# STM32F103RE.net
KiCad netlist of a schematic drawn in Altium Designer
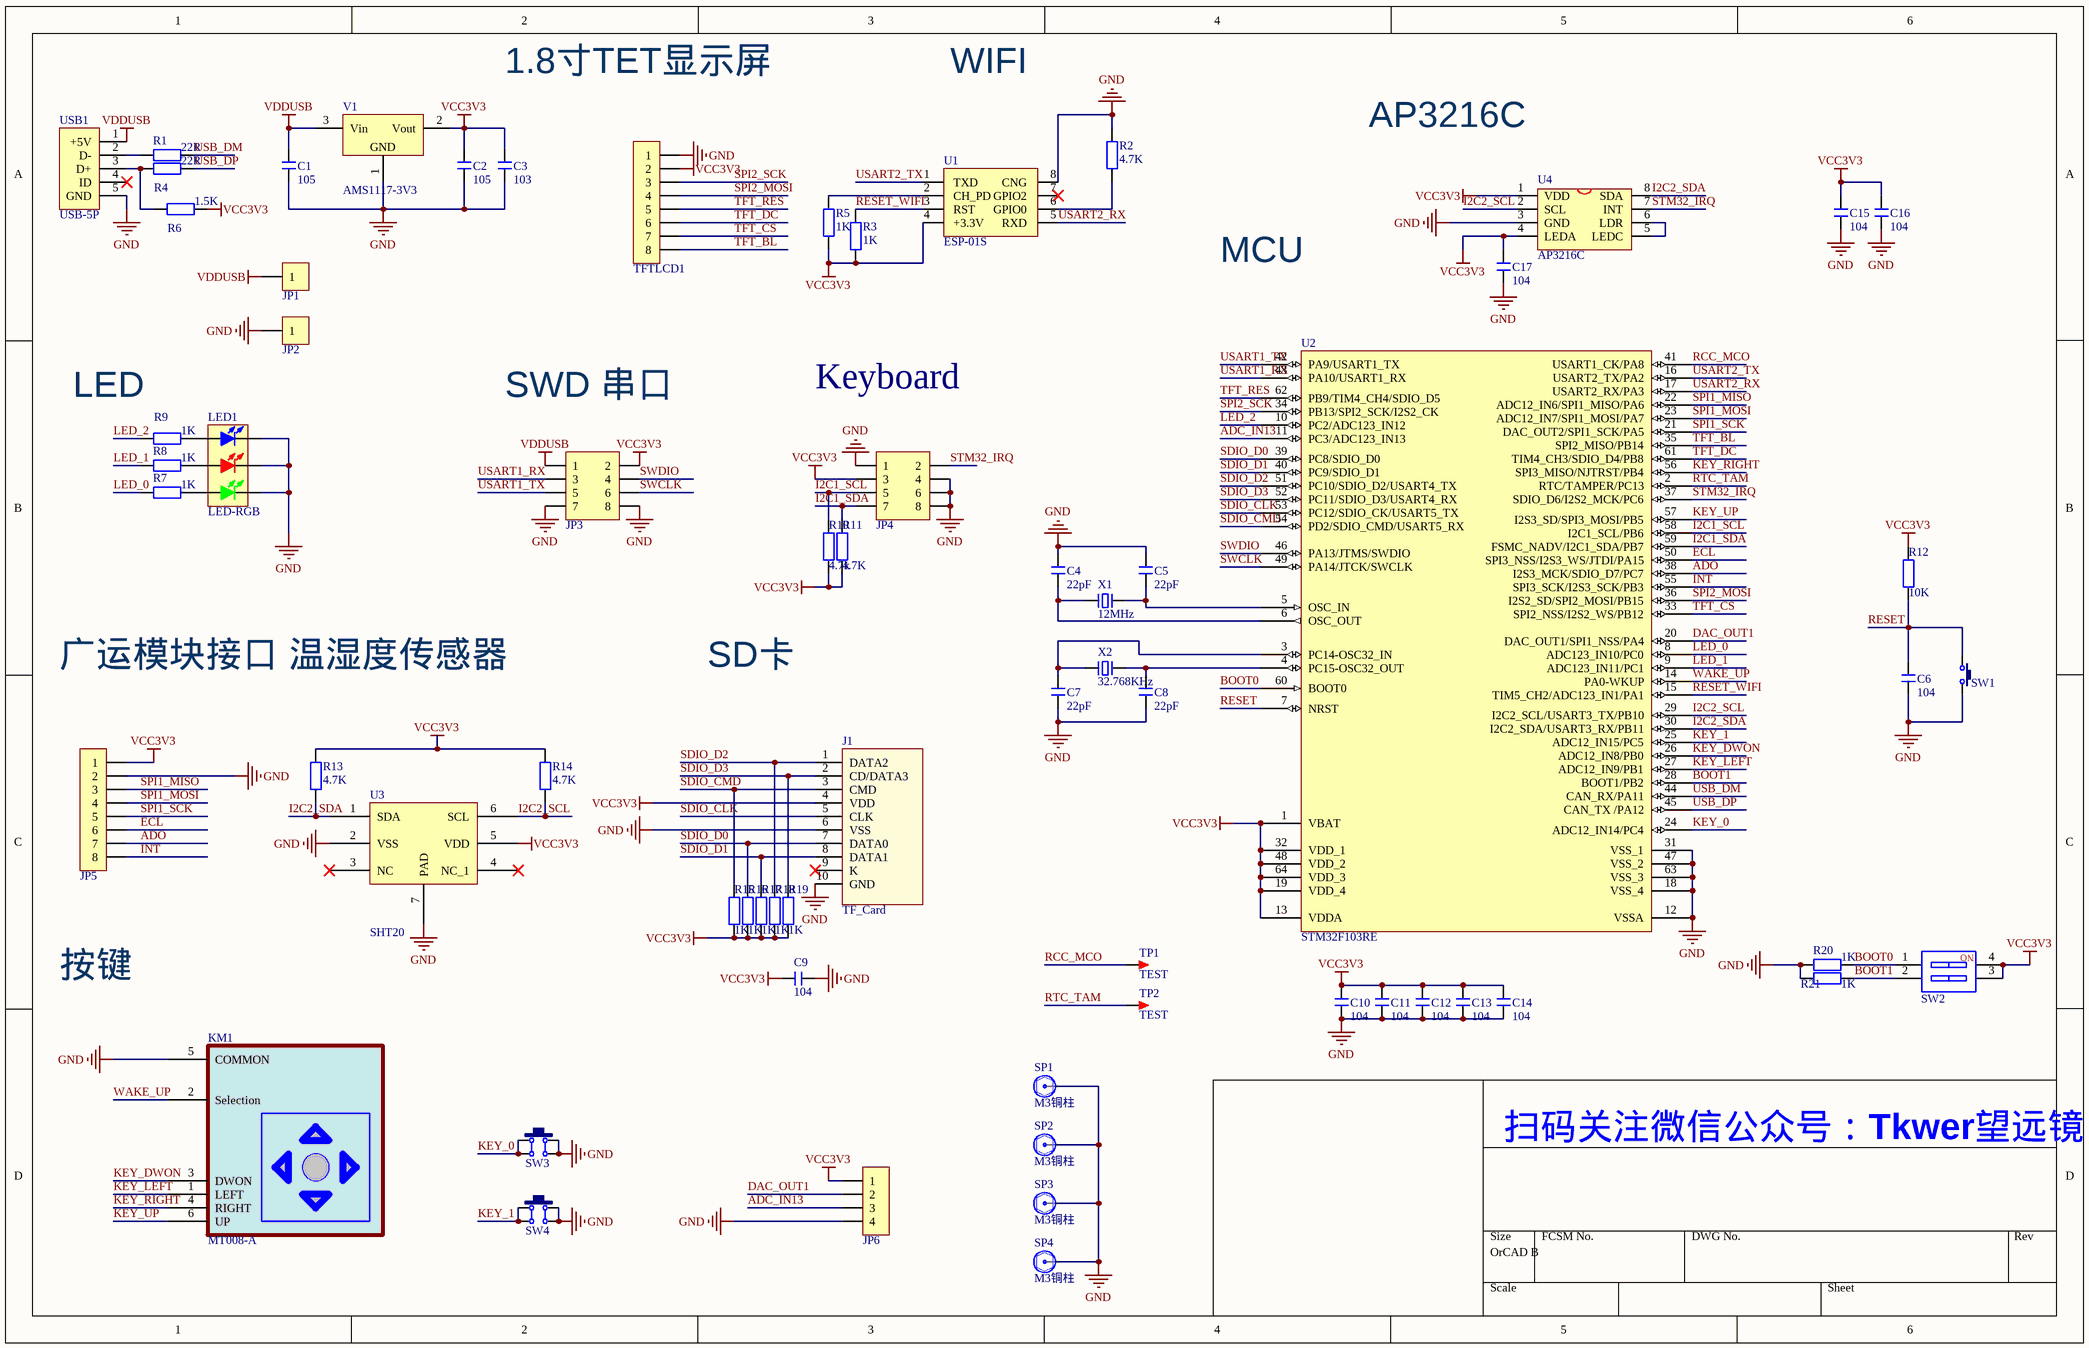
[diagram p0: STM32F103RE.SchDoc]

(export (version "E")
  (design (tool "Eeschema 10.0.6"))
  (components
    (comp (ref "C1")
      (value "105")
      (footprint "C 0805_L")
      (description "无极性贴片电容")
      (fields (field (name "版权归属") "源创客"))
      (libsource (lib "3.1   - 电阻-电容-电感") (part "C"))
    )
    (comp (ref "C2")
      (value "105")
      (footprint "C 0805_L")
      (description "无极性贴片电容")
      (fields (field (name "版权归属") "源创客"))
      (libsource (lib "3.1   - 电阻-电容-电感") (part "C"))
    )
    (comp (ref "C3")
      (value "103")
      (footprint "C 0603_L")
      (description "无极性贴片电容")
      (fields (field (name "版权归属") "源创客"))
      (libsource (lib "3.1   - 电阻-电容-电感") (part "C"))
    )
    (comp (ref "C4")
      (value "22pF")
      (footprint "C 0603_L")
      (description "无极性贴片电容")
      (fields (field (name "版权归属") "源创客"))
      (libsource (lib "3.1   - 电阻-电容-电感") (part "C"))
    )
    (comp (ref "C5")
      (value "22pF")
      (footprint "C 0603_L")
      (description "无极性贴片电容")
      (fields (field (name "版权归属") "源创客"))
      (libsource (lib "3.1   - 电阻-电容-电感") (part "C"))
    )
    (comp (ref "C6")
      (value "104")
      (footprint "C 0603_L")
      (description "无极性贴片电容")
      (fields (field (name "版权归属") "源创客"))
      (libsource (lib "3.1   - 电阻-电容-电感") (part "C"))
    )
    (comp (ref "C7")
      (value "22pF")
      (footprint "C 0603_L")
      (description "无极性贴片电容")
      (fields (field (name "版权归属") "源创客"))
      (libsource (lib "3.1   - 电阻-电容-电感") (part "C"))
    )
    (comp (ref "C8")
      (value "22pF")
      (footprint "C 0603_L")
      (description "无极性贴片电容")
      (fields (field (name "版权归属") "源创客"))
      (libsource (lib "3.1   - 电阻-电容-电感") (part "C"))
    )
    (comp (ref "C9")
      (value "104")
      (footprint "C 0603_L")
      (description "无极性贴片电容")
      (fields (field (name "版权归属") "源创客"))
      (libsource (lib "电阻-电容-电感") (part "C"))
    )
    (comp (ref "C10")
      (value "104")
      (footprint "C 0603_L")
      (description "无极性贴片电容")
      (fields (field (name "版权归属") "源创客"))
      (libsource (lib "3.1   - 电阻-电容-电感") (part "C"))
    )
    (comp (ref "C11")
      (value "104")
      (footprint "C 0603_L")
      (description "无极性贴片电容")
      (fields (field (name "版权归属") "源创客"))
      (libsource (lib "3.1   - 电阻-电容-电感") (part "C"))
    )
    (comp (ref "C12")
      (value "104")
      (footprint "C 0603_L")
      (description "无极性贴片电容")
      (fields (field (name "版权归属") "源创客"))
      (libsource (lib "3.1   - 电阻-电容-电感") (part "C"))
    )
    (comp (ref "C13")
      (value "104")
      (footprint "C 0603_L")
      (description "无极性贴片电容")
      (fields (field (name "版权归属") "源创客"))
      (libsource (lib "3.1   - 电阻-电容-电感") (part "C"))
    )
    (comp (ref "C14")
      (value "104")
      (footprint "C 0603_L")
      (description "无极性贴片电容")
      (fields (field (name "版权归属") "源创客"))
      (libsource (lib "3.1   - 电阻-电容-电感") (part "C"))
    )
    (comp (ref "C15")
      (value "104")
      (footprint "C 0603_L")
      (description "无极性贴片电容")
      (fields (field (name "版权归属") "源创客"))
      (libsource (lib "3.1   - 电阻-电容-电感") (part "C"))
    )
    (comp (ref "C16")
      (value "104")
      (footprint "C 0603_L")
      (description "无极性贴片电容")
      (fields (field (name "版权归属") "源创客"))
      (libsource (lib "3.1   - 电阻-电容-电感") (part "C"))
    )
    (comp (ref "C17")
      (value "104")
      (footprint "C 0603_L")
      (description "无极性贴片电容")
      (fields (field (name "版权归属") "源创客"))
      (libsource (lib "3.1   - 电阻-电容-电感") (part "C"))
    )
    (comp (ref "J1")
      (value "TF_Card")
      (footprint "Micro SD")
      (description "TF卡座")
      (fields (field (name "版权归属") "源创客"))
      (libsource (lib "4.1   - 接口类") (part "TF_Card"))
    )
    (comp (ref "JP1")
      (value "HDR-1X1")
      (footprint "HDR2.54-LI-1P")
      (description "1P接插件")
      (fields (field (name "版权归属") "源创客"))
      (libsource (lib "接插件") (part "Header 1"))
    )
    (comp (ref "JP2")
      (value "HDR-1X1")
      (footprint "HDR2.54-LI-1P")
      (description "1P接插件")
      (fields (field (name "版权归属") "源创客"))
      (libsource (lib "接插件") (part "Header 1"))
    )
    (comp (ref "JP3")
      (value "Header 4X2")
      (footprint "HDR2.54-WI-2x4P")
      (description "4*2P接插件")
      (fields (field (name "版权归属") "源创客"))
      (libsource (lib "4.5   - 接插件-脚距2.54") (part "Header 4X2"))
    )
    (comp (ref "JP4")
      (value "Header 4X2")
      (footprint "HDR2.54-WI-2x4P")
      (description "4*2P接插件")
      (fields (field (name "版权归属") "源创客"))
      (libsource (lib "4.5   - 接插件-脚距2.54") (part "Header 4X2"))
    )
    (comp (ref "JP5")
      (value "HDR-1X8")
      (footprint "HDR2.54-M-LI-8P")
      (description "8P接插件")
      (fields (field (name "版权归属") "源创客"))
      (libsource (lib "4.5   - 接插件-脚距2.54") (part "Header 8"))
    )
    (comp (ref "JP6")
      (value "HDR-1X4")
      (footprint "HDR2.54-LI-4P")
      (description "4P接插件")
      (fields (field (name "版权归属") "源创客"))
      (libsource (lib "4.5   - 接插件-脚距2.54") (part "Header 4"))
    )
    (comp (ref "KM1")
      (value "MT008-A")
      (footprint "JOY_MT008-A")
      (libsource (lib "13.1 - 模块") (part "MT-008A"))
    )
    (comp (ref "LED1")
      (value "LED-RGB")
      (footprint "LED 5050")
      (description "三基色LED")
      (fields (field (name "版权归属") "源创客"))
      (libsource (lib "9.1   - LED") (part "LED-RGB"))
    )
    (comp (ref "R1")
      (value "22R")
      (footprint "R 0603_L")
      (description "贴片电阻")
      (fields (field (name "版权归属") "源创客"))
      (libsource (lib "3.1   - 电阻-电容-电感") (part "R"))
    )
    (comp (ref "R2")
      (value "4.7K")
      (footprint "R 0603_L")
      (description "贴片电阻")
      (fields (field (name "版权归属") "源创客"))
      (libsource (lib "3.1   - 电阻-电容-电感") (part "R"))
    )
    (comp (ref "R3")
      (value "1K")
      (footprint "R 0603_L")
      (description "贴片电阻")
      (fields (field (name "版权归属") "源创客"))
      (libsource (lib "3.1   - 电阻-电容-电感") (part "R"))
    )
    (comp (ref "R4")
      (value "22R")
      (footprint "R 0603_L")
      (description "贴片电阻")
      (fields (field (name "版权归属") "源创客"))
      (libsource (lib "3.1   - 电阻-电容-电感") (part "R"))
    )
    (comp (ref "R5")
      (value "1K")
      (footprint "R 0603_L")
      (description "贴片电阻")
      (fields (field (name "版权归属") "源创客"))
      (libsource (lib "3.1   - 电阻-电容-电感") (part "R"))
    )
    (comp (ref "R6")
      (value "1.5K")
      (footprint "R 0603_L")
      (description "贴片电阻")
      (fields (field (name "版权归属") "源创客"))
      (libsource (lib "3.1   - 电阻-电容-电感") (part "R"))
    )
    (comp (ref "R7")
      (value "1K")
      (footprint "R 0603_L")
      (description "贴片电阻")
      (fields (field (name "版权归属") "源创客"))
      (libsource (lib "3.1   - 电阻-电容-电感") (part "R"))
    )
    (comp (ref "R8")
      (value "1K")
      (footprint "R 0603_L")
      (description "贴片电阻")
      (fields (field (name "版权归属") "源创客"))
      (libsource (lib "3.1   - 电阻-电容-电感") (part "R"))
    )
    (comp (ref "R9")
      (value "1K")
      (footprint "R 0603_L")
      (description "贴片电阻")
      (fields (field (name "版权归属") "源创客"))
      (libsource (lib "3.1   - 电阻-电容-电感") (part "R"))
    )
    (comp (ref "R10")
      (value "4.7k")
      (footprint "R 0603_L")
      (description "贴片电阻")
      (fields (field (name "版权归属") "源创客"))
      (libsource (lib "电阻-电容-电感") (part "R"))
    )
    (comp (ref "R11")
      (value "4.7K")
      (footprint "R 0603_L")
      (description "贴片电阻")
      (fields (field (name "版权归属") "源创客"))
      (libsource (lib "电阻-电容-电感") (part "R"))
    )
    (comp (ref "R12")
      (value "10K")
      (footprint "R 0603_L")
      (description "贴片电阻")
      (fields (field (name "版权归属") "源创客"))
      (libsource (lib "电阻-电容-电感") (part "R"))
    )
    (comp (ref "R13")
      (value "4.7K")
      (footprint "R 0603_L")
      (description "贴片电阻")
      (fields (field (name "版权归属") "源创客"))
      (libsource (lib "3.1   - 电阻-电容-电感") (part "R"))
    )
    (comp (ref "R14")
      (value "4.7K")
      (footprint "R 0603_L")
      (description "贴片电阻")
      (fields (field (name "版权归属") "源创客"))
      (libsource (lib "3.1   - 电阻-电容-电感") (part "R"))
    )
    (comp (ref "R15")
      (value "1K")
      (footprint "R 0603_L")
      (description "贴片电阻")
      (fields (field (name "版权归属") "源创客"))
      (libsource (lib "电阻-电容-电感") (part "R"))
    )
    (comp (ref "R16")
      (value "1K")
      (footprint "R 0603_L")
      (description "贴片电阻")
      (fields (field (name "版权归属") "源创客"))
      (libsource (lib "电阻-电容-电感") (part "R"))
    )
    (comp (ref "R17")
      (value "1K")
      (footprint "R 0603_L")
      (description "贴片电阻")
      (fields (field (name "版权归属") "源创客"))
      (libsource (lib "电阻-电容-电感") (part "R"))
    )
    (comp (ref "R18")
      (value "1K")
      (footprint "R 0603_L")
      (description "贴片电阻")
      (fields (field (name "版权归属") "源创客"))
      (libsource (lib "电阻-电容-电感") (part "R"))
    )
    (comp (ref "R19")
      (value "1K")
      (footprint "R 0603_L")
      (description "贴片电阻")
      (fields (field (name "版权归属") "源创客"))
      (libsource (lib "电阻-电容-电感") (part "R"))
    )
    (comp (ref "R20")
      (value "1K")
      (footprint "R 0603_L")
      (description "贴片电阻")
      (fields (field (name "版权归属") "源创客"))
      (libsource (lib "3.1   - 电阻-电容-电感") (part "R"))
    )
    (comp (ref "R21")
      (value "1K")
      (footprint "R 0603_L")
      (description "贴片电阻")
      (fields (field (name "版权归属") "源创客"))
      (libsource (lib "3.1   - 电阻-电容-电感") (part "R"))
    )
    (comp (ref "SP1")
      (value "M3铜柱")
      (footprint "M3x4_L")
      (description "铜柱")
      (fields (field (name "版权归属") "源创客"))
      (libsource (lib "15.1 - 未分类器件") (part "铜柱小焊盘"))
    )
    (comp (ref "SP2")
      (value "M3铜柱")
      (footprint "M3x4_L")
      (description "铜柱")
      (fields (field (name "版权归属") "源创客"))
      (libsource (lib "15.1 - 未分类器件") (part "铜柱小焊盘"))
    )
    (comp (ref "SP3")
      (value "M3铜柱")
      (footprint "M3x4_L")
      (description "铜柱")
      (fields (field (name "版权归属") "源创客"))
      (libsource (lib "15.1 - 未分类器件") (part "铜柱小焊盘"))
    )
    (comp (ref "SP4")
      (value "M3铜柱")
      (footprint "M3x4_L")
      (description "铜柱")
      (fields (field (name "版权归属") "源创客"))
      (libsource (lib "15.1 - 未分类器件") (part "铜柱小焊盘"))
    )
    (comp (ref "SW1")
      (value "3x6x5")
      (footprint "TSW SMD-3*6*2.5")
      (description "3x6轻触开关")
      (fields (field (name "版权归属") "源创客"))
      (libsource (lib "5.1   - 按键-开关") (part "TSW 3x6"))
    )
    (comp (ref "SW2")
      (value "CSW-2P")
      (footprint "CSW1.27 SMD-2P")
      (description "2路编码开关")
      (fields (field (name "版权归属") "源创客"))
      (libsource (lib "5.1   - 按键-开关") (part "CSW-2P"))
    )
    (comp (ref "SW3")
      (value "6x6x5")
      (footprint "SODFL700X110-2N")
      (description "贴片6x6轻触开关")
      (fields (field (name "版权归属") "源创客"))
      (libsource (lib "按键-开关") (part "TSW SMD-6x6"))
    )
    (comp (ref "SW4")
      (value "6x6x5")
      (footprint "SODFL700X110-2N")
      (description "贴片6x6轻触开关")
      (fields (field (name "版权归属") "源创客"))
      (libsource (lib "按键-开关") (part "TSW SMD-6x6"))
    )
    (comp (ref "TFTLCD1")
      (value "HDR-1X8")
      (footprint "HDR2.54-M-LI-8P")
      (description "8P接插件")
      (fields (field (name "版权归属") "源创客"))
      (libsource (lib "接插件") (part "Header 8"))
    )
    (comp (ref "TP1")
      (value "TEST")
      (footprint "TEST 1.6")
      (description "测试点")
      (fields (field (name "版权归属") "源创客"))
      (libsource (lib "15.1 - 未分类器件") (part "TEST"))
    )
    (comp (ref "TP2")
      (value "TEST")
      (footprint "TEST 1.6")
      (description "测试点")
      (fields (field (name "版权归属") "源创客"))
      (libsource (lib "15.1 - 未分类器件") (part "TEST"))
    )
    (comp (ref "U1") (value "ESP-01S") (footprint "ESP-01S") (libsource (lib "13.1 - 模块") (part "ESP-01S")))
    (comp (ref "U2")
      (value "STM32F103RE")
      (footprint "LQFP64 10X10_N")
      (description "32位STM单片机")
      (fields (field (name "版权归属") "源创客"))
      (libsource (lib "2.1   - STM32系列单片机") (part "STM32F103RE"))
    )
    (comp (ref "U3") (value "SHT20") (footprint "sht20") (libsource (lib "STM32F103RETX") (part "SHT20")))
    (comp (ref "U4")
      (value "AP3216C")
      (footprint "DFN8")
      (description "ALS+PS Sensor")
      (libsource (lib "MERCURY") (part "AP3216C"))
    )
    (comp (ref "USB1")
      (value "USB-5P")
      (footprint "USB-MICRO_A")
      (description "微型USB母座")
      (fields (field (name "版权归属") "源创客"))
      (libsource (lib "4.1   - 接口类") (part "USB-5P"))
    )
    (comp (ref "V1")
      (value "AMS1117-3V3")
      (footprint "SOT223_L")
      (description "三端稳压芯片")
      (fields (field (name "版权归属") "源创客"))
      (libsource (lib "1.3   - 电源类芯片") (part "AMS1117"))
    )
    (comp (ref "X1")
      (value "12MHz")
      (footprint "OSC 5032-2P")
      (description "2脚晶振")
      (fields (field (name "版权归属") "源创客"))
      (libsource (lib "保险丝-晶振") (part "XTAL-2"))
    )
    (comp (ref "X2")
      (value "32.768KHz")
      (footprint "XTAL-3215")
      (description "2脚晶振")
      (fields (field (name "版权归属") "源创客"))
      (libsource (lib "保险丝-晶振") (part "XTAL-2"))
    )
  )
  (nets
    (net (code "1") (name "/ADC_IN13") (class "Default")
      (node (ref "JP6") (pin "3") (pinfunction "3_3") (pintype "passive"))
      (node (ref "U2") (pin "11") (pinfunction "PC3/ADC123_IN13_11") (pintype "bidirectional"))
    )
    (net (code "2") (name "/ADO") (class "Default")
      (node (ref "JP5") (pin "7") (pinfunction "7_7") (pintype "passive"))
      (node (ref "U2") (pin "38") (pinfunction "I2S3_MCK/SDIO_D7/PC7_38") (pintype "bidirectional"))
    )
    (net (code "3") (name "/BOOT0") (class "Default")
      (node (ref "R20") (pin "2") (pinfunction "2_2") (pintype "passive"))
      (node (ref "SW2") (pin "1") (pinfunction "1_1") (pintype "passive"))
      (node (ref "U2") (pin "60") (pinfunction "BOOT0_60") (pintype "input"))
    )
    (net (code "4") (name "/BOOT1") (class "Default")
      (node (ref "R21") (pin "2") (pinfunction "2_2") (pintype "passive"))
      (node (ref "SW2") (pin "2") (pinfunction "2_2") (pintype "passive"))
      (node (ref "U2") (pin "28") (pinfunction "BOOT1/PB2_28") (pintype "bidirectional"))
    )
    (net (code "5") (name "/DAC_OUT1") (class "Default")
      (node (ref "JP6") (pin "2") (pinfunction "2_2") (pintype "passive"))
      (node (ref "U2") (pin "20") (pinfunction "DAC_OUT1/SPI1_NSS/PA4_20") (pintype "bidirectional"))
    )
    (net (code "6") (name "/ECL") (class "Default")
      (node (ref "JP5") (pin "6") (pinfunction "6_6") (pintype "passive"))
      (node (ref "U2") (pin "50") (pinfunction "SPI3_NSS/I2S3_WS/JTDI/PA15_50") (pintype "bidirectional"))
    )
    (net (code "7") (name "/I2C1_SCL") (class "Default")
      (node (ref "JP4") (pin "5") (pinfunction "5_5") (pintype "passive"))
      (node (ref "R10") (pin "2") (pinfunction "2_2") (pintype "passive"))
      (node (ref "U2") (pin "58") (pinfunction "I2C1_SCL/PB6_58") (pintype "bidirectional"))
    )
    (net (code "8") (name "/I2C1_SDA") (class "Default")
      (node (ref "JP4") (pin "7") (pinfunction "7_7") (pintype "passive"))
      (node (ref "R11") (pin "2") (pinfunction "2_2") (pintype "passive"))
      (node (ref "U2") (pin "59") (pinfunction "FSMC_NADV/I2C1_SDA/PB7_59") (pintype "bidirectional"))
    )
    (net (code "9") (name "/I2C2_SCL") (class "Default")
      (node (ref "R14") (pin "2") (pinfunction "2_2") (pintype "passive"))
      (node (ref "U2") (pin "29") (pinfunction "I2C2_SCL/USART3_TX/PB10_29") (pintype "bidirectional"))
      (node (ref "U3") (pin "6") (pinfunction "SCL_6") (pintype "passive"))
      (node (ref "U4") (pin "2") (pinfunction "SCL_2") (pintype "passive"))
    )
    (net (code "10") (name "/I2C2_SDA") (class "Default")
      (node (ref "R13") (pin "2") (pinfunction "2_2") (pintype "passive"))
      (node (ref "U2") (pin "30") (pinfunction "I2C2_SDA/USART3_RX/PB11_30") (pintype "bidirectional"))
      (node (ref "U3") (pin "1") (pinfunction "SDA_1") (pintype "passive"))
      (node (ref "U4") (pin "8") (pinfunction "SDA_8") (pintype "passive"))
    )
    (net (code "11") (name "/INT") (class "Default")
      (node (ref "JP5") (pin "8") (pinfunction "8_8") (pintype "passive"))
      (node (ref "U2") (pin "55") (pinfunction "SPI3_SCK/I2S3_SCK/PB3_55") (pintype "bidirectional"))
    )
    (net (code "12") (name "/KEY_0") (class "Default")
      (node (ref "SW3") (pin "1") (pinfunction "1_1") (pintype "passive"))
      (node (ref "SW3") (pin "4") (pinfunction "4_4") (pintype "passive"))
      (node (ref "U2") (pin "24") (pinfunction "ADC12_IN14/PC4_24") (pintype "bidirectional"))
    )
    (net (code "13") (name "/KEY_1") (class "Default")
      (node (ref "SW4") (pin "1") (pinfunction "1_1") (pintype "passive"))
      (node (ref "SW4") (pin "4") (pinfunction "4_4") (pintype "passive"))
      (node (ref "U2") (pin "25") (pinfunction "ADC12_IN15/PC5_25") (pintype "bidirectional"))
    )
    (net (code "14") (name "/KEY_DWON") (class "Default")
      (node (ref "KM1") (pin "3") (pinfunction "DWON_3") (pintype "passive"))
      (node (ref "U2") (pin "26") (pinfunction "ADC12_IN8/PB0_26") (pintype "bidirectional"))
    )
    (net (code "15") (name "/KEY_LEFT") (class "Default")
      (node (ref "KM1") (pin "1") (pinfunction "LEFT_1") (pintype "passive"))
      (node (ref "U2") (pin "27") (pinfunction "ADC12_IN9/PB1_27") (pintype "bidirectional"))
    )
    (net (code "16") (name "/KEY_RIGHT") (class "Default")
      (node (ref "KM1") (pin "4") (pinfunction "RIGHT_4") (pintype "passive"))
      (node (ref "U2") (pin "56") (pinfunction "SPI3_MISO/NJTRST/PB4_56") (pintype "bidirectional"))
    )
    (net (code "17") (name "/KEY_UP") (class "Default")
      (node (ref "KM1") (pin "6") (pinfunction "UP_6") (pintype "passive"))
      (node (ref "U2") (pin "57") (pinfunction "I2S3_SD/SPI3_MOSI/PB5_57") (pintype "bidirectional"))
    )
    (net (code "18") (name "/LED_0") (class "Default")
      (node (ref "R7") (pin "2") (pinfunction "2_2") (pintype "passive"))
      (node (ref "U2") (pin "8") (pinfunction "ADC123_IN10/PC0_8") (pintype "bidirectional"))
    )
    (net (code "19") (name "/LED_1") (class "Default")
      (node (ref "R8") (pin "2") (pinfunction "2_2") (pintype "passive"))
      (node (ref "U2") (pin "9") (pinfunction "ADC123_IN11/PC1_9") (pintype "bidirectional"))
    )
    (net (code "20") (name "/LED_2") (class "Default")
      (node (ref "R9") (pin "2") (pinfunction "2_2") (pintype "passive"))
      (node (ref "U2") (pin "10") (pinfunction "PC2/ADC123_IN12_10") (pintype "bidirectional"))
    )
    (net (code "21") (name "/RCC_MCO") (class "Default")
      (node (ref "TP1") (pin "1") (pinfunction "1_1") (pintype "passive"))
      (node (ref "U2") (pin "41") (pinfunction "USART1_CK/PA8_41") (pintype "bidirectional"))
    )
    (net (code "22") (name "/RESET") (class "Default")
      (node (ref "C6") (pin "2") (pinfunction "2_2") (pintype "passive"))
      (node (ref "R12") (pin "1") (pinfunction "1_1") (pintype "passive"))
      (node (ref "SW1") (pin "1") (pinfunction "1_1") (pintype "passive"))
      (node (ref "U2") (pin "7") (pinfunction "NRST_7") (pintype "bidirectional"))
    )
    (net (code "23") (name "/RESET_WIFI") (class "Default")
      (node (ref "R3") (pin "1") (pinfunction "1_1") (pintype "passive"))
      (node (ref "U1") (pin "3") (pinfunction "RST_3") (pintype "passive"))
      (node (ref "U2") (pin "15") (pinfunction "TIM5_CH2/ADC123_IN1/PA1_15") (pintype "bidirectional"))
    )
    (net (code "24") (name "/RTC_TAM") (class "Default")
      (node (ref "TP2") (pin "1") (pinfunction "1_1") (pintype "passive"))
      (node (ref "U2") (pin "2") (pinfunction "RTC/TAMPER/PC13_2") (pintype "bidirectional"))
    )
    (net (code "25") (name "/SDIO_CLK") (class "Default")
      (node (ref "J1") (pin "5") (pinfunction "CLK_5") (pintype "passive"))
      (node (ref "U2") (pin "53") (pinfunction "PC12/SDIO_CK/USART5_TX_53") (pintype "bidirectional"))
    )
    (net (code "26") (name "/SDIO_CMD") (class "Default")
      (node (ref "J1") (pin "3") (pinfunction "CMD_3") (pintype "passive"))
      (node (ref "R15") (pin "2") (pinfunction "2_2") (pintype "passive"))
      (node (ref "U2") (pin "54") (pinfunction "PD2/SDIO_CMD/USART5_RX_54") (pintype "bidirectional"))
    )
    (net (code "27") (name "/SDIO_D0") (class "Default")
      (node (ref "J1") (pin "7") (pinfunction "DATA0_7") (pintype "passive"))
      (node (ref "R16") (pin "2") (pinfunction "2_2") (pintype "passive"))
      (node (ref "U2") (pin "39") (pinfunction "PC8/SDIO_D0_39") (pintype "bidirectional"))
    )
    (net (code "28") (name "/SDIO_D1") (class "Default")
      (node (ref "J1") (pin "8") (pinfunction "DATA1_8") (pintype "passive"))
      (node (ref "R17") (pin "2") (pinfunction "2_2") (pintype "passive"))
      (node (ref "U2") (pin "40") (pinfunction "PC9/SDIO_D1_40") (pintype "bidirectional"))
    )
    (net (code "29") (name "/SDIO_D2") (class "Default")
      (node (ref "J1") (pin "1") (pinfunction "DATA2_1") (pintype "passive"))
      (node (ref "R18") (pin "2") (pinfunction "2_2") (pintype "passive"))
      (node (ref "U2") (pin "51") (pinfunction "PC10/SDIO_D2/USART4_TX_51") (pintype "bidirectional"))
    )
    (net (code "30") (name "/SDIO_D3") (class "Default")
      (node (ref "J1") (pin "2") (pinfunction "CD/DATA3_2") (pintype "passive"))
      (node (ref "R19") (pin "2") (pinfunction "2_2") (pintype "passive"))
      (node (ref "U2") (pin "52") (pinfunction "PC11/SDIO_D3/USART4_RX_52") (pintype "bidirectional"))
    )
    (net (code "31") (name "/SPI1_MISO") (class "Default")
      (node (ref "JP5") (pin "3") (pinfunction "3_3") (pintype "passive"))
      (node (ref "U2") (pin "22") (pinfunction "ADC12_IN6/SPI1_MISO/PA6_22") (pintype "bidirectional"))
    )
    (net (code "32") (name "/SPI1_MOSI") (class "Default")
      (node (ref "JP5") (pin "4") (pinfunction "4_4") (pintype "passive"))
      (node (ref "U2") (pin "23") (pinfunction "ADC12_IN7/SPI1_MOSI/PA7_23") (pintype "bidirectional"))
    )
    (net (code "33") (name "/SPI1_SCK") (class "Default")
      (node (ref "JP5") (pin "5") (pinfunction "5_5") (pintype "passive"))
      (node (ref "U2") (pin "21") (pinfunction "DAC_OUT2/SPI1_SCK/PA5_21") (pintype "bidirectional"))
    )
    (net (code "34") (name "/SPI2_MOSI") (class "Default")
      (node (ref "TFTLCD1") (pin "4") (pinfunction "4_4") (pintype "passive"))
      (node (ref "U2") (pin "36") (pinfunction "I2S2_SD/SPI2_MOSI/PB15_36") (pintype "bidirectional"))
    )
    (net (code "35") (name "/SPI2_SCK") (class "Default")
      (node (ref "TFTLCD1") (pin "3") (pinfunction "3_3") (pintype "passive"))
      (node (ref "U2") (pin "34") (pinfunction "PB13/SPI2_SCK/I2S2_CK_34") (pintype "bidirectional"))
    )
    (net (code "36") (name "/STM32_IRQ") (class "Default")
      (node (ref "JP4") (pin "2") (pinfunction "2_2") (pintype "passive"))
      (node (ref "U2") (pin "37") (pinfunction "SDIO_D6/I2S2_MCK/PC6_37") (pintype "bidirectional"))
      (node (ref "U4") (pin "7") (pinfunction "INT_7") (pintype "passive"))
    )
    (net (code "37") (name "/SWCLK") (class "Default")
      (node (ref "JP3") (pin "6") (pinfunction "6_6") (pintype "passive"))
      (node (ref "U2") (pin "49") (pinfunction "PA14/JTCK/SWCLK_49") (pintype "bidirectional"))
    )
    (net (code "38") (name "/SWDIO") (class "Default")
      (node (ref "JP3") (pin "4") (pinfunction "4_4") (pintype "passive"))
      (node (ref "U2") (pin "46") (pinfunction "PA13/JTMS/SWDIO_46") (pintype "bidirectional"))
    )
    (net (code "39") (name "/TFT_BL") (class "Default")
      (node (ref "TFTLCD1") (pin "8") (pinfunction "8_8") (pintype "passive"))
      (node (ref "U2") (pin "35") (pinfunction "SPI2_MISO/PB14_35") (pintype "bidirectional"))
    )
    (net (code "40") (name "/TFT_CS") (class "Default")
      (node (ref "TFTLCD1") (pin "7") (pinfunction "7_7") (pintype "passive"))
      (node (ref "U2") (pin "33") (pinfunction "SPI2_NSS/I2S2_WS/PB12_33") (pintype "bidirectional"))
    )
    (net (code "41") (name "/TFT_DC") (class "Default")
      (node (ref "TFTLCD1") (pin "6") (pinfunction "6_6") (pintype "passive"))
      (node (ref "U2") (pin "61") (pinfunction "TIM4_CH3/SDIO_D4/PB8_61") (pintype "bidirectional"))
    )
    (net (code "42") (name "/TFT_RES") (class "Default")
      (node (ref "TFTLCD1") (pin "5") (pinfunction "5_5") (pintype "passive"))
      (node (ref "U2") (pin "62") (pinfunction "PB9/TIM4_CH4/SDIO_D5_62") (pintype "bidirectional"))
    )
    (net (code "43") (name "/USART1_RX") (class "Default")
      (node (ref "JP3") (pin "3") (pinfunction "3_3") (pintype "passive"))
      (node (ref "U2") (pin "43") (pinfunction "PA10/USART1_RX_43") (pintype "bidirectional"))
    )
    (net (code "44") (name "/USART1_TX") (class "Default")
      (node (ref "JP3") (pin "5") (pinfunction "5_5") (pintype "passive"))
      (node (ref "U2") (pin "42") (pinfunction "PA9/USART1_TX_42") (pintype "bidirectional"))
    )
    (net (code "45") (name "/USART2_RX") (class "Default")
      (node (ref "U1") (pin "5") (pinfunction "RXD_5") (pintype "passive"))
      (node (ref "U2") (pin "17") (pinfunction "USART2_RX/PA3_17") (pintype "bidirectional"))
    )
    (net (code "46") (name "/USART2_TX") (class "Default")
      (node (ref "U1") (pin "1") (pinfunction "TXD_1") (pintype "passive"))
      (node (ref "U2") (pin "16") (pinfunction "USART2_TX/PA2_16") (pintype "bidirectional"))
    )
    (net (code "47") (name "/USB_DM") (class "Default")
      (node (ref "R1") (pin "1") (pinfunction "1_1") (pintype "passive"))
      (node (ref "U2") (pin "44") (pinfunction "CAN_RX/PA11_44") (pintype "bidirectional"))
    )
    (net (code "48") (name "/USB_DP") (class "Default")
      (node (ref "R4") (pin "1") (pinfunction "1_1") (pintype "passive"))
      (node (ref "U2") (pin "45") (pinfunction "CAN_TX_/PA12_45") (pintype "bidirectional"))
    )
    (net (code "49") (name "/WAKE_UP") (class "Default")
      (node (ref "KM1") (pin "2") (pinfunction "Selection_2") (pintype "passive"))
      (node (ref "U2") (pin "14") (pinfunction "PA0-WKUP_14") (pintype "bidirectional"))
    )
    (net (code "50") (name "GND") (class "Default")
      (node (ref "C1") (pin "1") (pinfunction "1_1") (pintype "passive"))
      (node (ref "C10") (pin "1") (pinfunction "1_1") (pintype "passive"))
      (node (ref "C11") (pin "1") (pinfunction "1_1") (pintype "passive"))
      (node (ref "C12") (pin "1") (pinfunction "1_1") (pintype "passive"))
      (node (ref "C13") (pin "1") (pinfunction "1_1") (pintype "passive"))
      (node (ref "C14") (pin "1") (pinfunction "1_1") (pintype "passive"))
      (node (ref "C15") (pin "2") (pinfunction "2_2") (pintype "passive"))
      (node (ref "C16") (pin "2") (pinfunction "2_2") (pintype "passive"))
      (node (ref "C17") (pin "2") (pinfunction "2_2") (pintype "passive"))
      (node (ref "C2") (pin "1") (pinfunction "1_1") (pintype "passive"))
      (node (ref "C3") (pin "1") (pinfunction "1_1") (pintype "passive"))
      (node (ref "C4") (pin "2") (pinfunction "2_2") (pintype "passive"))
      (node (ref "C5") (pin "2") (pinfunction "2_2") (pintype "passive"))
      (node (ref "C6") (pin "1") (pinfunction "1_1") (pintype "passive"))
      (node (ref "C7") (pin "1") (pinfunction "1_1") (pintype "passive"))
      (node (ref "C8") (pin "1") (pinfunction "1_1") (pintype "passive"))
      (node (ref "C9") (pin "2") (pinfunction "2_2") (pintype "passive"))
      (node (ref "J1") (pin "10") (pinfunction "GND_10") (pintype "passive"))
      (node (ref "J1") (pin "6") (pinfunction "VSS_6") (pintype "passive"))
      (node (ref "JP2") (pin "1") (pinfunction "1_1") (pintype "passive"))
      (node (ref "JP3") (pin "7") (pinfunction "7_7") (pintype "passive"))
      (node (ref "JP3") (pin "8") (pinfunction "8_8") (pintype "passive"))
      (node (ref "JP4") (pin "1") (pinfunction "1_1") (pintype "passive"))
      (node (ref "JP4") (pin "4") (pinfunction "4_4") (pintype "passive"))
      (node (ref "JP4") (pin "6") (pinfunction "6_6") (pintype "passive"))
      (node (ref "JP4") (pin "8") (pinfunction "8_8") (pintype "passive"))
      (node (ref "JP5") (pin "2") (pinfunction "2_2") (pintype "passive"))
      (node (ref "JP6") (pin "4") (pinfunction "4_4") (pintype "passive"))
      (node (ref "KM1") (pin "5") (pinfunction "COMMON_5") (pintype "passive"))
      (node (ref "LED1") (pin "2") (pinfunction "BULE_K_2") (pintype "passive"))
      (node (ref "LED1") (pin "4") (pinfunction "RED_K_4") (pintype "passive"))
      (node (ref "LED1") (pin "6") (pinfunction "GREEN_K_6") (pintype "passive"))
      (node (ref "R2") (pin "2") (pinfunction "2_2") (pintype "passive"))
      (node (ref "R20") (pin "1") (pinfunction "1_1") (pintype "passive"))
      (node (ref "R21") (pin "1") (pinfunction "1_1") (pintype "passive"))
      (node (ref "SP1") (pin "1") (pinfunction "1_1") (pintype "passive"))
      (node (ref "SP2") (pin "1") (pinfunction "1_1") (pintype "passive"))
      (node (ref "SP3") (pin "1") (pinfunction "1_1") (pintype "passive"))
      (node (ref "SP4") (pin "1") (pinfunction "1_1") (pintype "passive"))
      (node (ref "SW1") (pin "2") (pinfunction "2_2") (pintype "passive"))
      (node (ref "SW3") (pin "2") (pinfunction "2_2") (pintype "passive"))
      (node (ref "SW3") (pin "3") (pinfunction "3_3") (pintype "passive"))
      (node (ref "SW4") (pin "2") (pinfunction "2_2") (pintype "passive"))
      (node (ref "SW4") (pin "3") (pinfunction "3_3") (pintype "passive"))
      (node (ref "TFTLCD1") (pin "1") (pinfunction "1_1") (pintype "passive"))
      (node (ref "U1") (pin "8") (pinfunction "CNG_8") (pintype "passive"))
      (node (ref "U2") (pin "12") (pinfunction "VSSA_12") (pintype "power_in"))
      (node (ref "U2") (pin "18") (pinfunction "VSS_4_18") (pintype "power_in"))
      (node (ref "U2") (pin "31") (pinfunction "VSS_1_31") (pintype "passive"))
      (node (ref "U2") (pin "47") (pinfunction "VSS_2_47") (pintype "passive"))
      (node (ref "U2") (pin "63") (pinfunction "VSS_3_63") (pintype "power_in"))
      (node (ref "U3") (pin "2") (pinfunction "VSS_2") (pintype "passive"))
      (node (ref "U3") (pin "7") (pinfunction "PAD_7") (pintype "passive"))
      (node (ref "U4") (pin "3") (pinfunction "GND_3") (pintype "passive"))
      (node (ref "USB1") (pin "5") (pinfunction "GND_5") (pintype "passive"))
      (node (ref "V1") (pin "1") (pinfunction "GND_1") (pintype "passive"))
    )
    (net (code "51") (name "Net-(LED1-BULE_A)") (class "Default")
      (node (ref "LED1") (pin "1") (pinfunction "BULE_A_1") (pintype "passive"))
      (node (ref "R9") (pin "1") (pinfunction "1_1") (pintype "passive"))
    )
    (net (code "52") (name "Net-(LED1-GREEN_A)") (class "Default")
      (node (ref "LED1") (pin "5") (pinfunction "GREEN_A_5") (pintype "passive"))
      (node (ref "R7") (pin "1") (pinfunction "1_1") (pintype "passive"))
    )
    (net (code "53") (name "Net-(LED1-RED_A)") (class "Default")
      (node (ref "LED1") (pin "3") (pinfunction "RED_A_3") (pintype "passive"))
      (node (ref "R8") (pin "1") (pinfunction "1_1") (pintype "passive"))
    )
    (net (code "54") (name "Net-(U1-CH_PD)") (class "Default")
      (node (ref "R5") (pin "1") (pinfunction "1_1") (pintype "passive"))
      (node (ref "U1") (pin "2") (pinfunction "CH_PD_2") (pintype "passive"))
    )
    (net (code "55") (name "Net-(U1-GPIO0)") (class "Default")
      (node (ref "R2") (pin "1") (pinfunction "1_1") (pintype "passive"))
      (node (ref "U1") (pin "6") (pinfunction "GPIO0_6") (pintype "passive"))
    )
    (net (code "56") (name "Net-(U2-OSC_IN)") (class "Default")
      (node (ref "C5") (pin "1") (pinfunction "1_1") (pintype "passive"))
      (node (ref "U2") (pin "5") (pinfunction "OSC_IN_5") (pintype "input"))
      (node (ref "X1") (pin "1") (pinfunction "1_1") (pintype "passive"))
    )
    (net (code "57") (name "Net-(U2-OSC_OUT)") (class "Default")
      (node (ref "C4") (pin "1") (pinfunction "1_1") (pintype "passive"))
      (node (ref "U2") (pin "6") (pinfunction "OSC_OUT_6") (pintype "output"))
      (node (ref "X1") (pin "2") (pinfunction "2_2") (pintype "passive"))
    )
    (net (code "58") (name "Net-(U2-PC14-OSC32_IN)") (class "Default")
      (node (ref "C7") (pin "2") (pinfunction "2_2") (pintype "passive"))
      (node (ref "U2") (pin "3") (pinfunction "PC14-OSC32_IN_3") (pintype "bidirectional"))
      (node (ref "X2") (pin "2") (pinfunction "2_2") (pintype "passive"))
    )
    (net (code "59") (name "Net-(U2-PC15-OSC32_OUT)") (class "Default")
      (node (ref "C8") (pin "2") (pinfunction "2_2") (pintype "passive"))
      (node (ref "U2") (pin "4") (pinfunction "PC15-OSC32_OUT_4") (pintype "bidirectional"))
      (node (ref "X2") (pin "1") (pinfunction "1_1") (pintype "passive"))
    )
    (net (code "60") (name "Net-(U4-LDR)") (class "Default")
      (node (ref "U4") (pin "5") (pinfunction "LEDC_5") (pintype "passive"))
      (node (ref "U4") (pin "6") (pinfunction "LDR_6") (pintype "passive"))
    )
    (net (code "61") (name "Net-(USB1-D+)") (class "Default")
      (node (ref "R4") (pin "2") (pinfunction "2_2") (pintype "passive"))
      (node (ref "R6") (pin "2") (pinfunction "2_2") (pintype "passive"))
      (node (ref "USB1") (pin "3") (pinfunction "D+_3") (pintype "passive"))
    )
    (net (code "62") (name "Net-(USB1-D-)") (class "Default")
      (node (ref "R1") (pin "2") (pinfunction "2_2") (pintype "passive"))
      (node (ref "USB1") (pin "2") (pinfunction "D-_2") (pintype "passive"))
    )
    (net (code "63") (name "VCC3V3") (class "Default")
      (node (ref "C10") (pin "2") (pinfunction "2_2") (pintype "passive"))
      (node (ref "C11") (pin "2") (pinfunction "2_2") (pintype "passive"))
      (node (ref "C12") (pin "2") (pinfunction "2_2") (pintype "passive"))
      (node (ref "C13") (pin "2") (pinfunction "2_2") (pintype "passive"))
      (node (ref "C14") (pin "2") (pinfunction "2_2") (pintype "passive"))
      (node (ref "C15") (pin "1") (pinfunction "1_1") (pintype "passive"))
      (node (ref "C16") (pin "1") (pinfunction "1_1") (pintype "passive"))
      (node (ref "C17") (pin "1") (pinfunction "1_1") (pintype "passive"))
      (node (ref "C2") (pin "2") (pinfunction "2_2") (pintype "passive"))
      (node (ref "C3") (pin "2") (pinfunction "2_2") (pintype "passive"))
      (node (ref "C9") (pin "1") (pinfunction "1_1") (pintype "passive"))
      (node (ref "J1") (pin "4") (pinfunction "VDD_4") (pintype "passive"))
      (node (ref "JP3") (pin "2") (pinfunction "2_2") (pintype "passive"))
      (node (ref "JP4") (pin "3") (pinfunction "3_3") (pintype "passive"))
      (node (ref "JP5") (pin "1") (pinfunction "1_1") (pintype "passive"))
      (node (ref "JP6") (pin "1") (pinfunction "1_1") (pintype "passive"))
      (node (ref "R10") (pin "1") (pinfunction "1_1") (pintype "passive"))
      (node (ref "R11") (pin "1") (pinfunction "1_1") (pintype "passive"))
      (node (ref "R12") (pin "2") (pinfunction "2_2") (pintype "passive"))
      (node (ref "R13") (pin "1") (pinfunction "1_1") (pintype "passive"))
      (node (ref "R14") (pin "1") (pinfunction "1_1") (pintype "passive"))
      (node (ref "R15") (pin "1") (pinfunction "1_1") (pintype "passive"))
      (node (ref "R16") (pin "1") (pinfunction "1_1") (pintype "passive"))
      (node (ref "R17") (pin "1") (pinfunction "1_1") (pintype "passive"))
      (node (ref "R18") (pin "1") (pinfunction "1_1") (pintype "passive"))
      (node (ref "R19") (pin "1") (pinfunction "1_1") (pintype "passive"))
      (node (ref "R3") (pin "2") (pinfunction "2_2") (pintype "passive"))
      (node (ref "R5") (pin "2") (pinfunction "2_2") (pintype "passive"))
      (node (ref "R6") (pin "1") (pinfunction "1_1") (pintype "passive"))
      (node (ref "SW2") (pin "3") (pinfunction "3_3") (pintype "passive"))
      (node (ref "SW2") (pin "4") (pinfunction "4_4") (pintype "passive"))
      (node (ref "TFTLCD1") (pin "2") (pinfunction "2_2") (pintype "passive"))
      (node (ref "U1") (pin "4") (pinfunction "+3.3V_4") (pintype "passive"))
      (node (ref "U2") (pin "1") (pinfunction "VBAT_1") (pintype "power_in"))
      (node (ref "U2") (pin "13") (pinfunction "VDDA_13") (pintype "power_in"))
      (node (ref "U2") (pin "19") (pinfunction "VDD_4_19") (pintype "power_in"))
      (node (ref "U2") (pin "32") (pinfunction "VDD_1_32") (pintype "power_in"))
      (node (ref "U2") (pin "48") (pinfunction "VDD_2_48") (pintype "power_in"))
      (node (ref "U2") (pin "64") (pinfunction "VDD_3_64") (pintype "power_in"))
      (node (ref "U3") (pin "5") (pinfunction "VDD_5") (pintype "passive"))
      (node (ref "U4") (pin "1") (pinfunction "VDD_1") (pintype "passive"))
      (node (ref "U4") (pin "4") (pinfunction "LEDA_4") (pintype "passive"))
      (node (ref "V1") (pin "2") (pinfunction "Vout_2") (pintype "passive"))
    )
    (net (code "64") (name "VDDUSB") (class "Default")
      (node (ref "C1") (pin "2") (pinfunction "2_2") (pintype "passive"))
      (node (ref "JP1") (pin "1") (pinfunction "1_1") (pintype "passive"))
      (node (ref "JP3") (pin "1") (pinfunction "1_1") (pintype "passive"))
      (node (ref "USB1") (pin "1") (pinfunction "+5V_1") (pintype "passive"))
      (node (ref "V1") (pin "3") (pinfunction "Vin_3") (pintype "passive"))
    )
    (net (code "65") (name "unconnected-(J1-K-Pad9)") (class "Default")
      (node (ref "J1") (pin "9") (pinfunction "K_9") (pintype "passive+no_connect"))
    )
    (net (code "66") (name "unconnected-(U1-GPIO2-Pad7)") (class "Default")
      (node (ref "U1") (pin "7") (pinfunction "GPIO2_7") (pintype "passive+no_connect"))
    )
    (net (code "67") (name "unconnected-(U3-NC-Pad3)") (class "Default")
      (node (ref "U3") (pin "3") (pinfunction "NC_3") (pintype "passive+no_connect"))
    )
    (net (code "68") (name "unconnected-(U3-NC_1-Pad4)") (class "Default")
      (node (ref "U3") (pin "4") (pinfunction "NC_1_4") (pintype "passive+no_connect"))
    )
    (net (code "69") (name "unconnected-(USB1-ID-Pad4)") (class "Default")
      (node (ref "USB1") (pin "4") (pinfunction "ID_4") (pintype "passive+no_connect"))
    )
  )
)
